# Signal_Gen.net
KiCad netlist of a schematic drawn in EAGLE
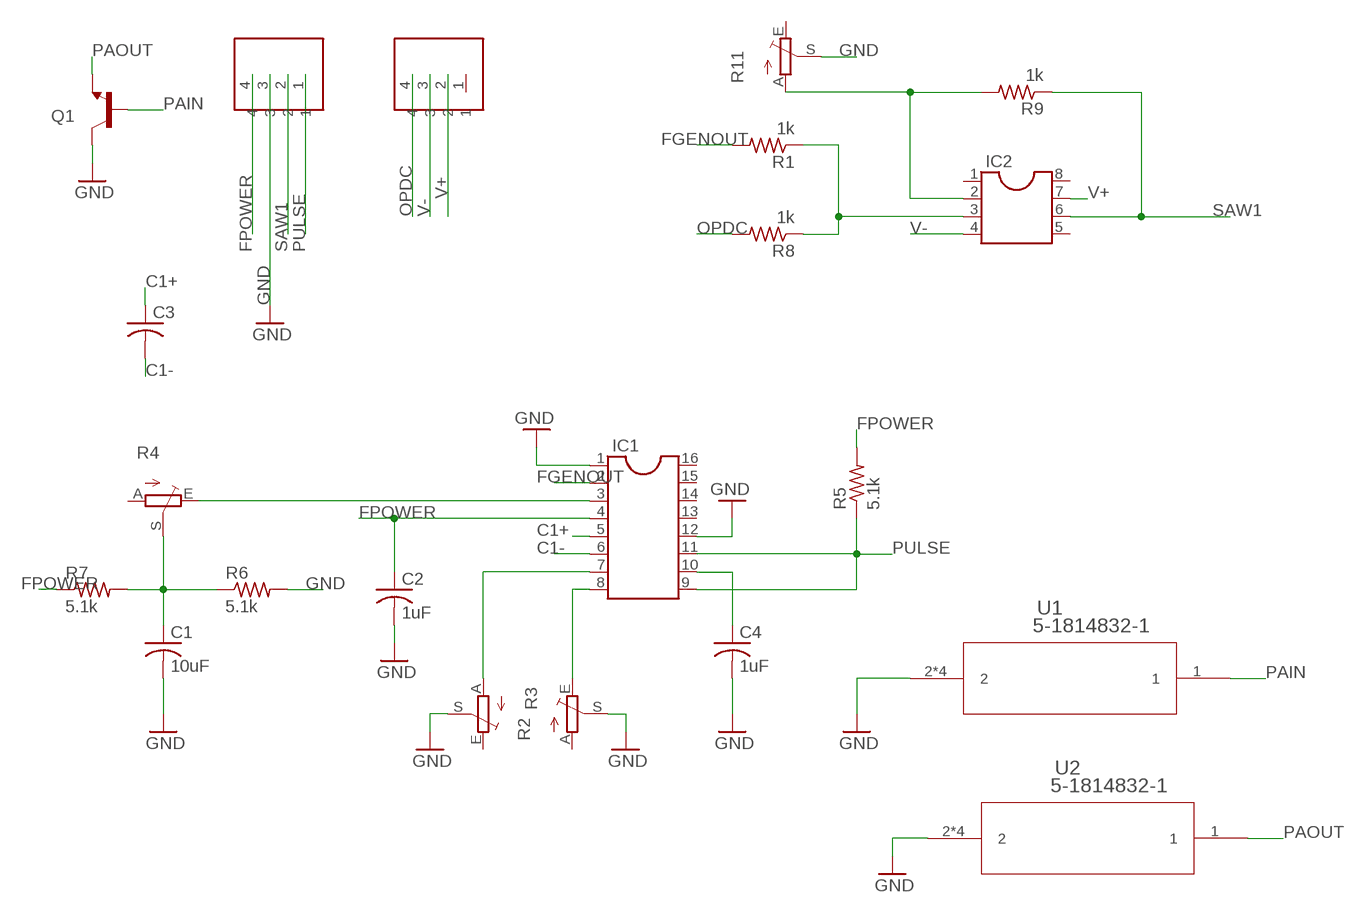
[diagram p0: schematic, sheet 1]

(export (version "E")
  (design (tool "Eeschema 10.0.6"))
  (components
    (comp (ref "C1")
      (value "10uF")
      (footprint "eagle-import:C025-025X050")
      (libsource (lib "eagle-import") (part "C-US025-025X050"))
    )
    (comp (ref "C2")
      (value "1uF")
      (footprint "eagle-import:C025-025X050")
      (libsource (lib "eagle-import") (part "C-US025-025X050"))
    )
    (comp (ref "C3")
      (value "C-US025-025X050")
      (footprint "eagle-import:C025-025X050")
      (libsource (lib "eagle-import") (part "C-US025-025X050"))
    )
    (comp (ref "C4")
      (value "1uF")
      (footprint "eagle-import:C025-025X050")
      (libsource (lib "eagle-import") (part "C-US025-025X050"))
    )
    (comp (ref "IC1")
      (value "DIL16S")
      (footprint "eagle-import:SOCKET-16")
      (libsource (lib "eagle-import") (part "DIL16S"))
    )
    (comp (ref "IC2")
      (value "DIL8S")
      (footprint "eagle-import:SOCKET-08")
      (libsource (lib "eagle-import") (part "DIL8S"))
    )
    (comp (ref "Q1")
      (value "TRANSISTOR_NPNSOT89")
      (footprint "eagle-import:SOT89")
      (libsource (lib "eagle-import") (part "TRANSISTOR_NPNSOT89"))
    )
    (comp (ref "R1")
      (value "1k")
      (footprint "eagle-import:0204_7")
      (libsource (lib "eagle-import") (part "R-US_0204/7"))
    )
    (comp (ref "R2")
      (value "TRIM_EU-B25U")
      (footprint "eagle-import:B25U")
      (libsource (lib "eagle-import") (part "TRIM_EU-B25U"))
    )
    (comp (ref "R3")
      (value "TRIM_EU-B25U")
      (footprint "eagle-import:B25U")
      (libsource (lib "eagle-import") (part "TRIM_EU-B25U"))
    )
    (comp (ref "R4")
      (value "TRIM_EU-B64W")
      (footprint "eagle-import:B64W")
      (libsource (lib "eagle-import") (part "TRIM_EU-B64W"))
    )
    (comp (ref "R5")
      (value "5.1k")
      (footprint "eagle-import:0204_7")
      (libsource (lib "eagle-import") (part "R-US_0204/7"))
    )
    (comp (ref "R6")
      (value "5.1k")
      (footprint "eagle-import:0204_7")
      (libsource (lib "eagle-import") (part "R-US_0204/7"))
    )
    (comp (ref "R7")
      (value "5.1k")
      (footprint "eagle-import:0204_7")
      (libsource (lib "eagle-import") (part "R-US_0204/7"))
    )
    (comp (ref "R8")
      (value "1k")
      (footprint "eagle-import:0204_7")
      (libsource (lib "eagle-import") (part "R-US_0204/7"))
    )
    (comp (ref "R9")
      (value "1k")
      (footprint "eagle-import:0204_7")
      (libsource (lib "eagle-import") (part "R-US_0204/7"))
    )
    (comp (ref "R11")
      (value "TRIM_EU-RJ9W")
      (footprint "eagle-import:RJ9W")
      (libsource (lib "eagle-import") (part "TRIM_EU-RJ9W"))
    )
    (comp (ref "U$1")
      (value "ED2582-ND")
      (footprint "eagle-import:ED2582-ND")
      (libsource (lib "eagle-import") (part "ED2582-ND"))
    )
    (comp (ref "U$2")
      (value "ED2582-ND")
      (footprint "eagle-import:ED2582-ND")
      (libsource (lib "eagle-import") (part "ED2582-ND"))
    )
    (comp (ref "U1")
      (value "5-1814832-1")
      (footprint "eagle-import:5-1814832-1")
      (fields (field (name "COPYRIGHT") "Copyright (C) 2015 Accelerated Designs. All rights reserved"))
      (libsource (lib "eagle-import") (part "5-1814832-1"))
    )
    (comp (ref "U2")
      (value "5-1814832-1")
      (footprint "eagle-import:5-1814832-1")
      (fields (field (name "COPYRIGHT") "Copyright (C) 2015 Accelerated Designs. All rights reserved"))
      (libsource (lib "eagle-import") (part "5-1814832-1"))
    )
  )
  (nets
    (net (code "1") (name "/C1+") (class "Default")
      (node (ref "C3") (pin "1") (pinfunction "1_1") (pintype "passive"))
      (node (ref "IC1") (pin "5") (pinfunction "5_5") (pintype "passive"))
    )
    (net (code "2") (name "/C1-") (class "Default")
      (node (ref "C3") (pin "2") (pinfunction "2_2") (pintype "passive"))
      (node (ref "IC1") (pin "6") (pinfunction "6_6") (pintype "passive"))
    )
    (net (code "3") (name "/FGENOUT") (class "Default")
      (node (ref "IC1") (pin "2") (pinfunction "2_2") (pintype "passive"))
      (node (ref "R1") (pin "2") (pinfunction "2_2") (pintype "passive"))
    )
    (net (code "4") (name "/FPOWER") (class "Default")
      (node (ref "C2") (pin "1") (pinfunction "1_1") (pintype "passive"))
      (node (ref "IC1") (pin "4") (pinfunction "4_4") (pintype "passive"))
      (node (ref "R5") (pin "2") (pinfunction "2_2") (pintype "passive"))
      (node (ref "R7") (pin "1") (pinfunction "1_1") (pintype "passive"))
      (node (ref "U$1") (pin "4") (pinfunction "4_4") (pintype "bidirectional"))
    )
    (net (code "5") (name "/OPDC") (class "Default")
      (node (ref "R8") (pin "2") (pinfunction "2_2") (pintype "passive"))
      (node (ref "U$2") (pin "4") (pinfunction "4_4") (pintype "bidirectional"))
    )
    (net (code "6") (name "/PAIN") (class "Default")
      (node (ref "Q1") (pin "1") (pinfunction "B_1") (pintype "passive"))
      (node (ref "U1") (pin "1") (pinfunction "1_1") (pintype "passive"))
    )
    (net (code "7") (name "/PAOUT") (class "Default")
      (node (ref "Q1") (pin "3") (pinfunction "E_3") (pintype "passive"))
      (node (ref "U2") (pin "1") (pinfunction "1_1") (pintype "passive"))
    )
    (net (code "8") (name "/PULSE") (class "Default")
      (node (ref "IC1") (pin "11") (pinfunction "11_11") (pintype "passive"))
      (node (ref "IC1") (pin "9") (pinfunction "9_9") (pintype "passive"))
      (node (ref "R5") (pin "1") (pinfunction "1_1") (pintype "passive"))
      (node (ref "U$1") (pin "1") (pinfunction "1_1") (pintype "bidirectional"))
    )
    (net (code "9") (name "/SAW1") (class "Default")
      (node (ref "IC2") (pin "6") (pinfunction "6_6") (pintype "passive"))
      (node (ref "R9") (pin "1") (pinfunction "1_1") (pintype "passive"))
      (node (ref "U$1") (pin "2") (pinfunction "2_2") (pintype "bidirectional"))
    )
    (net (code "10") (name "/V+") (class "Default")
      (node (ref "IC2") (pin "7") (pinfunction "7_7") (pintype "passive"))
      (node (ref "U$2") (pin "2") (pinfunction "2_2") (pintype "bidirectional"))
    )
    (net (code "11") (name "/V-") (class "Default")
      (node (ref "IC2") (pin "4") (pinfunction "4_4") (pintype "passive"))
      (node (ref "U$2") (pin "3") (pinfunction "3_3") (pintype "bidirectional"))
    )
    (net (code "12") (name "GND") (class "Default")
      (node (ref "C1") (pin "2") (pinfunction "2_2") (pintype "passive"))
      (node (ref "C2") (pin "2") (pinfunction "2_2") (pintype "passive"))
      (node (ref "C4") (pin "2") (pinfunction "2_2") (pintype "passive"))
      (node (ref "IC1") (pin "1") (pinfunction "1_1") (pintype "passive"))
      (node (ref "IC1") (pin "12") (pinfunction "12_12") (pintype "passive"))
      (node (ref "Q1") (pin "2") (pinfunction "C_2") (pintype "passive"))
      (node (ref "R11") (pin "S") (pinfunction "S_S") (pintype "passive"))
      (node (ref "R2") (pin "S") (pinfunction "S_S") (pintype "passive"))
      (node (ref "R3") (pin "S") (pinfunction "S_S") (pintype "passive"))
      (node (ref "R6") (pin "2") (pinfunction "2_2") (pintype "passive"))
      (node (ref "U$1") (pin "3") (pinfunction "3_3") (pintype "bidirectional"))
      (node (ref "U1") (pin "2") (pinfunction "2_2") (pintype "passive"))
      (node (ref "U1") (pin "3") (pinfunction "2_3") (pintype "passive"))
      (node (ref "U1") (pin "4") (pinfunction "2_4") (pintype "passive"))
      (node (ref "U1") (pin "5") (pinfunction "2_5") (pintype "passive"))
      (node (ref "U2") (pin "2") (pinfunction "2_2") (pintype "passive"))
      (node (ref "U2") (pin "3") (pinfunction "2_3") (pintype "passive"))
      (node (ref "U2") (pin "4") (pinfunction "2_4") (pintype "passive"))
      (node (ref "U2") (pin "5") (pinfunction "2_5") (pintype "passive"))
    )
    (net (code "13") (name "Net-(C1-Pad1)") (class "Default")
      (node (ref "C1") (pin "1") (pinfunction "1_1") (pintype "passive"))
      (node (ref "R4") (pin "S") (pinfunction "S_S") (pintype "passive"))
      (node (ref "R6") (pin "1") (pinfunction "1_1") (pintype "passive"))
      (node (ref "R7") (pin "2") (pinfunction "2_2") (pintype "passive"))
    )
    (net (code "14") (name "Net-(C4-Pad1)") (class "Default")
      (node (ref "C4") (pin "1") (pinfunction "1_1") (pintype "passive"))
      (node (ref "IC1") (pin "10") (pinfunction "10_10") (pintype "passive"))
    )
    (net (code "15") (name "Net-(IC1-Pad3)") (class "Default")
      (node (ref "IC1") (pin "3") (pinfunction "3_3") (pintype "passive"))
      (node (ref "R4") (pin "E") (pinfunction "E_E") (pintype "passive"))
    )
    (net (code "16") (name "Net-(IC1-Pad7)") (class "Default")
      (node (ref "IC1") (pin "7") (pinfunction "7_7") (pintype "passive"))
      (node (ref "R3") (pin "A") (pinfunction "A_A") (pintype "passive"))
    )
    (net (code "17") (name "Net-(IC1-Pad8)") (class "Default")
      (node (ref "IC1") (pin "8") (pinfunction "8_8") (pintype "passive"))
      (node (ref "R2") (pin "E") (pinfunction "E_E") (pintype "passive"))
    )
    (net (code "18") (name "Net-(IC2-Pad2)") (class "Default")
      (node (ref "IC2") (pin "2") (pinfunction "2_2") (pintype "passive"))
      (node (ref "R11") (pin "A") (pinfunction "A_A") (pintype "passive"))
      (node (ref "R9") (pin "2") (pinfunction "2_2") (pintype "passive"))
    )
    (net (code "19") (name "Net-(IC2-Pad3)") (class "Default")
      (node (ref "IC2") (pin "3") (pinfunction "3_3") (pintype "passive"))
      (node (ref "R1") (pin "1") (pinfunction "1_1") (pintype "passive"))
      (node (ref "R8") (pin "1") (pinfunction "1_1") (pintype "passive"))
    )
    (net (code "20") (name "unconnected-(IC1-Pad13)") (class "Default")
      (node (ref "IC1") (pin "13") (pinfunction "13_13") (pintype "passive"))
    )
    (net (code "21") (name "unconnected-(IC1-Pad14)") (class "Default")
      (node (ref "IC1") (pin "14") (pinfunction "14_14") (pintype "passive"))
    )
    (net (code "22") (name "unconnected-(IC1-Pad15)") (class "Default")
      (node (ref "IC1") (pin "15") (pinfunction "15_15") (pintype "passive"))
    )
    (net (code "23") (name "unconnected-(IC1-Pad16)") (class "Default")
      (node (ref "IC1") (pin "16") (pinfunction "16_16") (pintype "passive"))
    )
    (net (code "24") (name "unconnected-(IC2-Pad1)") (class "Default")
      (node (ref "IC2") (pin "1") (pinfunction "1_1") (pintype "passive"))
    )
    (net (code "25") (name "unconnected-(IC2-Pad5)") (class "Default")
      (node (ref "IC2") (pin "5") (pinfunction "5_5") (pintype "passive"))
    )
    (net (code "26") (name "unconnected-(IC2-Pad8)") (class "Default")
      (node (ref "IC2") (pin "8") (pinfunction "8_8") (pintype "passive"))
    )
    (net (code "27") (name "unconnected-(R2-PadA)") (class "Default")
      (node (ref "R2") (pin "A") (pinfunction "A_A") (pintype "passive"))
    )
    (net (code "28") (name "unconnected-(R3-PadE)") (class "Default")
      (node (ref "R3") (pin "E") (pinfunction "E_E") (pintype "passive"))
    )
    (net (code "29") (name "unconnected-(R4-PadA)") (class "Default")
      (node (ref "R4") (pin "A") (pinfunction "A_A") (pintype "passive"))
    )
    (net (code "30") (name "unconnected-(R11-PadE)") (class "Default")
      (node (ref "R11") (pin "E") (pinfunction "E_E") (pintype "passive"))
    )
    (net (code "31") (name "unconnected-(U$2-Pad1)") (class "Default")
      (node (ref "U$2") (pin "1") (pinfunction "1_1") (pintype "bidirectional"))
    )
  )
)
